# 4_Port__schdoc.net
KiCad netlist of a schematic drawn in Altium Designer
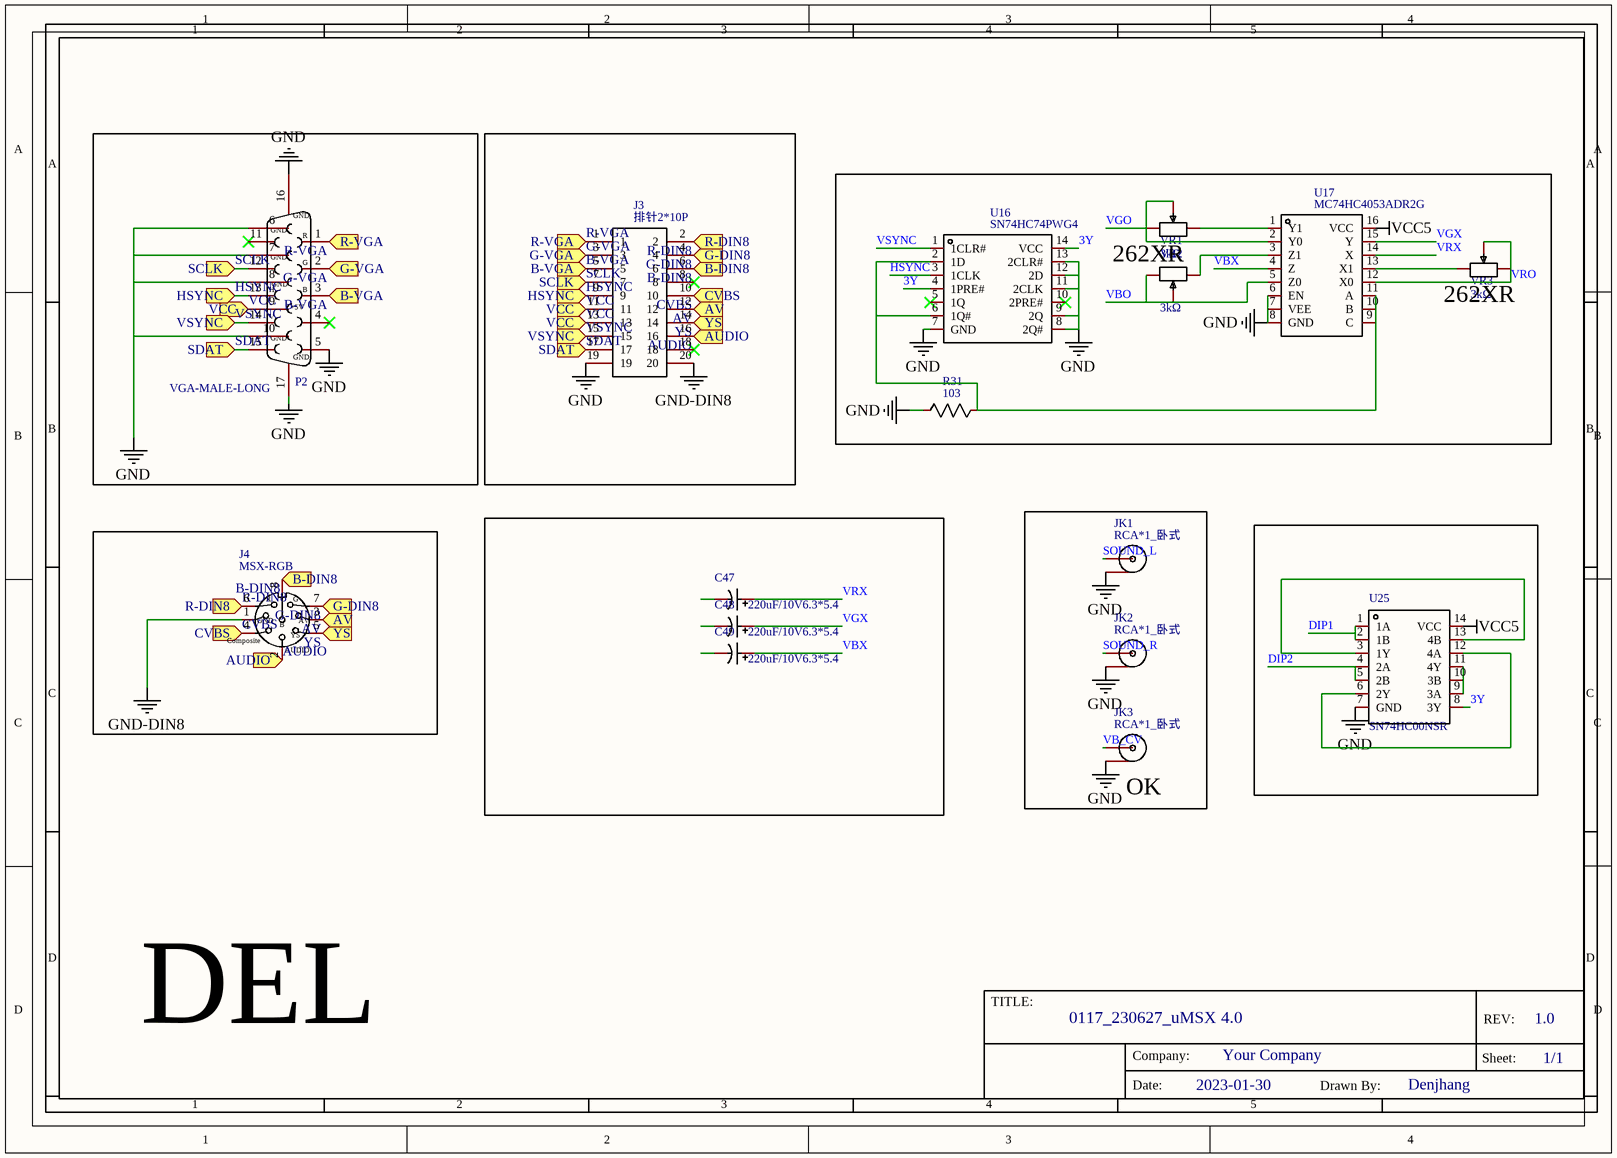
[diagram p0: 4_Port_多余的.schdoc.schdoc]

(export (version "E")
  (design (tool "Eeschema 10.0.6"))
  (components
    (comp (ref "C47")
      (value "220uF/10V6.3*5.4")
      (fields (field (name "NAME") "220uF/10V6.3*5.4"))
      (libsource (lib "altium-import") (part "root_2_固态电容220uF/10V6.3*5.4_"))
    )
    (comp (ref "C48")
      (value "220uF/10V6.3*5.4")
      (fields (field (name "NAME") "220uF/10V6.3*5.4"))
      (libsource (lib "altium-import") (part "root_2_固态电容220uF/10V6.3*5.4_"))
    )
    (comp (ref "C49")
      (value "220uF/10V6.3*5.4")
      (fields (field (name "NAME") "220uF/10V6.3*5.4"))
      (libsource (lib "altium-import") (part "root_2_固态电容220uF/10V6.3*5.4_"))
    )
    (comp (ref "J3")
      (value "排针2*10P")
      (fields (field (name "NAME") "排针2*10P"))
      (libsource (lib "altium-import") (part "root_0_排针2*10P_"))
    )
    (comp (ref "J4")
      (value "MSX-RGB")
      (fields (field (name "NAME") "MSX-RGB"))
      (libsource (lib "altium-import") (part "root_0_MSX-RGB_"))
    )
    (comp (ref "JK1")
      (value "RCA*1_卧式")
      (fields (field (name "NAME") "RCA*1_卧式"))
      (libsource (lib "altium-import") (part "root_3_RCA*1_卧式_"))
    )
    (comp (ref "JK2")
      (value "RCA*1_卧式")
      (fields (field (name "NAME") "RCA*1_卧式"))
      (libsource (lib "altium-import") (part "root_3_RCA*1_卧式_"))
    )
    (comp (ref "JK3")
      (value "RCA*1_卧式")
      (fields (field (name "NAME") "RCA*1_卧式"))
      (libsource (lib "altium-import") (part "root_3_RCA*1_卧式_"))
    )
    (comp (ref "P2")
      (value "VGA-MALE-LONG")
      (fields (field (name "NAME") "VGA-MALE-LONG"))
      (libsource (lib "altium-import") (part "root_0_VGA-MALE-LONG_"))
    )
    (comp (ref "R31")
      (value "103")
      (fields (field (name "NAME") "103"))
      (libsource (lib "altium-import") (part "root_0_103_"))
    )
    (comp (ref "U16")
      (value "SN74HC74PWG4")
      (fields (field (name "NAME") "SN74HC74PWG4") (field (name "MANUFACTURER") "TI(德州仪器)"))
      (libsource (lib "altium-import") (part "root_0_SN74HC74PWG4_"))
    )
    (comp (ref "U17")
      (value "MC74HC4053ADR2G")
      (fields (field (name "NAME") "MC74HC4053ADR2G") (field (name "MANUFACTURER") "onsemi(安森美)"))
      (libsource (lib "altium-import") (part "root_3_MC74HC4053ADR2G_"))
    )
    (comp (ref "U25")
      (value "SN74HC00NSR")
      (description "逻辑电路的归属系列:74HC;逻辑类型:与非门;")
      (fields (field (name "NAME") "SN74HC00NSR") (field (name "MANUFACTURER") "TI(德州仪器)"))
      (libsource (lib "altium-import") (part "root_0_SN74HC00NSR_"))
    )
    (comp (ref "VR1")
      (value "3kΩ")
      (fields
        (field (name "NAME") "3kΩ")
        (field (name "MANUFACTURER") "PANASONIC(松下)")
        (field (name "MANUFACTURER PART") "EVM3ESX50B33")
        (field (name "TOLERANCE") "±25%")
      )
      (libsource (lib "altium-import") (part "root_3_EVM3ESX50B33_"))
    )
    (comp (ref "VR2")
      (value "3kΩ")
      (fields
        (field (name "NAME") "3kΩ")
        (field (name "MANUFACTURER") "PANASONIC(松下)")
        (field (name "MANUFACTURER PART") "EVM3ESX50B33")
        (field (name "TOLERANCE") "±25%")
      )
      (libsource (lib "altium-import") (part "root_1_EVM3ESX50B33_"))
    )
    (comp (ref "VR3")
      (value "3kΩ")
      (fields
        (field (name "NAME") "3kΩ")
        (field (name "MANUFACTURER") "PANASONIC(松下)")
        (field (name "MANUFACTURER PART") "EVM3ESX50B33")
        (field (name "TOLERANCE") "±25%")
      )
      (libsource (lib "altium-import") (part "root_3_EVM3ESX50B33_"))
    )
  )
  (nets
    (net (code "1") (name "/3Y") (class "Default")
      (node (ref "U16") (pin "14") (pinfunction "VCC_14") (pintype "passive"))
      (node (ref "U16") (pin "4") (pinfunction "1PRE#_4") (pintype "passive"))
      (node (ref "U25") (pin "8") (pinfunction "3Y_8") (pintype "passive"))
    )
    (net (code "2") (name "/AUDIO") (class "Default")
      (node (ref "J3") (pin "16") (pinfunction "16_16") (pintype "passive"))
      (node (ref "J4") (pin "2") (pintype "passive"))
    )
    (net (code "3") (name "/AV") (class "Default")
      (node (ref "J3") (pin "12") (pinfunction "12_12") (pintype "passive"))
      (node (ref "J4") (pin "3") (pintype "passive"))
    )
    (net (code "4") (name "/B-DIN8") (class "Default")
      (node (ref "J3") (pin "6") (pinfunction "6_6") (pintype "passive"))
      (node (ref "J4") (pin "8") (pintype "passive"))
    )
    (net (code "5") (name "/B-VGA") (class "Default")
      (node (ref "J3") (pin "5") (pinfunction "5_5") (pintype "passive"))
      (node (ref "P2") (pin "3") (pinfunction "3_3") (pintype "passive"))
    )
    (net (code "6") (name "/CVBS") (class "Default")
      (node (ref "J3") (pin "10") (pinfunction "10_10") (pintype "passive"))
      (node (ref "J4") (pin "4") (pintype "passive"))
    )
    (net (code "7") (name "/DIP1") (class "Default")
      (node (ref "U25") (pin "1") (pinfunction "1A_1") (pintype "passive"))
      (node (ref "U25") (pin "2") (pinfunction "1B_2") (pintype "passive"))
    )
    (net (code "8") (name "/DIP2") (class "Default")
      (node (ref "U25") (pin "4") (pinfunction "2A_4") (pintype "passive"))
      (node (ref "U25") (pin "5") (pinfunction "2B_5") (pintype "passive"))
    )
    (net (code "9") (name "/G-DIN8") (class "Default")
      (node (ref "J3") (pin "4") (pinfunction "4_4") (pintype "passive"))
      (node (ref "J4") (pin "7") (pintype "passive"))
    )
    (net (code "10") (name "/G-VGA") (class "Default")
      (node (ref "J3") (pin "3") (pinfunction "3_3") (pintype "passive"))
      (node (ref "P2") (pin "2") (pinfunction "2_2") (pintype "passive"))
    )
    (net (code "11") (name "/HSYNC") (class "Default")
      (node (ref "J3") (pin "9") (pinfunction "9_9") (pintype "passive"))
      (node (ref "P2") (pin "13") (pinfunction "13_13") (pintype "passive"))
      (node (ref "U16") (pin "3") (pinfunction "1CLK_3") (pintype "passive"))
    )
    (net (code "12") (name "/R-DIN8") (class "Default")
      (node (ref "J3") (pin "2") (pinfunction "2_2") (pintype "passive"))
      (node (ref "J4") (pin "6") (pintype "passive"))
    )
    (net (code "13") (name "/R-VGA") (class "Default")
      (node (ref "J3") (pin "1") (pinfunction "1_1") (pintype "passive"))
      (node (ref "P2") (pin "1") (pinfunction "1_1") (pintype "passive"))
    )
    (net (code "14") (name "/SCLK") (class "Default")
      (node (ref "J3") (pin "7") (pinfunction "7_7") (pintype "passive"))
      (node (ref "P2") (pin "12") (pinfunction "12_12") (pintype "passive"))
    )
    (net (code "15") (name "/SDAT") (class "Default")
      (node (ref "J3") (pin "17") (pinfunction "17_17") (pintype "passive"))
      (node (ref "P2") (pin "15") (pinfunction "15_15") (pintype "passive"))
    )
    (net (code "16") (name "/SOUND_L") (class "Default")
      (node (ref "JK1") (pin "2") (pinfunction "2_2") (pintype "passive"))
    )
    (net (code "17") (name "/SOUND_R") (class "Default")
      (node (ref "JK2") (pin "2") (pinfunction "2_2") (pintype "passive"))
    )
    (net (code "18") (name "/VBO") (class "Default")
      (node (ref "U17") (pin "5") (pinfunction "Z0_5") (pintype "passive"))
      (node (ref "VR2") (pin "a") (pinfunction "a_a") (pintype "passive"))
      (node (ref "VR2") (pin "b") (pinfunction "b_b") (pintype "passive"))
    )
    (net (code "19") (name "/VBX") (class "Default")
      (node (ref "C49") (pin "1") (pinfunction "1_1") (pintype "passive"))
      (node (ref "U17") (pin "4") (pinfunction "Z_4") (pintype "passive"))
    )
    (net (code "20") (name "/VB_CV") (class "Default")
      (node (ref "JK3") (pin "2") (pinfunction "2_2") (pintype "passive"))
    )
    (net (code "21") (name "/VCC") (class "Default")
      (node (ref "J3") (pin "11") (pinfunction "11_11") (pintype "passive"))
      (node (ref "J3") (pin "13") (pinfunction "13_13") (pintype "passive"))
      (node (ref "P2") (pin "9") (pinfunction "9_9") (pintype "passive"))
    )
    (net (code "22") (name "/VGO") (class "Default")
      (node (ref "U17") (pin "2") (pinfunction "Y0_2") (pintype "passive"))
      (node (ref "VR1") (pin "b") (pinfunction "b_b") (pintype "passive"))
      (node (ref "VR1") (pin "c") (pinfunction "c_c") (pintype "passive"))
    )
    (net (code "23") (name "/VGX") (class "Default")
      (node (ref "C48") (pin "1") (pinfunction "1_1") (pintype "passive"))
      (node (ref "U17") (pin "15") (pinfunction "Y_15") (pintype "passive"))
    )
    (net (code "24") (name "/VRO") (class "Default")
      (node (ref "U17") (pin "12") (pinfunction "X0_12") (pintype "passive"))
      (node (ref "VR3") (pin "a") (pinfunction "a_a") (pintype "passive"))
      (node (ref "VR3") (pin "b") (pinfunction "b_b") (pintype "passive"))
    )
    (net (code "25") (name "/VRX") (class "Default")
      (node (ref "C47") (pin "1") (pinfunction "1_1") (pintype "passive"))
      (node (ref "U17") (pin "14") (pinfunction "X_14") (pintype "passive"))
    )
    (net (code "26") (name "/VSYNC") (class "Default")
      (node (ref "J3") (pin "15") (pinfunction "15_15") (pintype "passive"))
      (node (ref "P2") (pin "14") (pinfunction "14_14") (pintype "passive"))
      (node (ref "U16") (pin "1") (pinfunction "1CLR#_1") (pintype "passive"))
    )
    (net (code "27") (name "/YS") (class "Default")
      (node (ref "J3") (pin "14") (pinfunction "14_14") (pintype "passive"))
      (node (ref "J4") (pin "5") (pintype "passive"))
    )
    (net (code "28") (name "GND") (class "Default")
      (node (ref "J3") (pin "19") (pinfunction "19_19") (pintype "passive"))
      (node (ref "JK1") (pin "3") (pinfunction "3_3") (pintype "passive"))
      (node (ref "JK2") (pin "3") (pinfunction "3_3") (pintype "passive"))
      (node (ref "JK3") (pin "3") (pinfunction "3_3") (pintype "passive"))
      (node (ref "P2") (pin "10") (pinfunction "10_10") (pintype "passive"))
      (node (ref "P2") (pin "16") (pinfunction "0_16") (pintype "passive"))
      (node (ref "P2") (pin "17") (pinfunction "0_17") (pintype "passive"))
      (node (ref "P2") (pin "5") (pinfunction "5_5") (pintype "passive"))
      (node (ref "P2") (pin "6") (pinfunction "6_6") (pintype "passive"))
      (node (ref "P2") (pin "7") (pinfunction "7_7") (pintype "passive"))
      (node (ref "P2") (pin "8") (pinfunction "8_8") (pintype "passive"))
      (node (ref "R31") (pin "1") (pinfunction "1_1") (pintype "passive"))
      (node (ref "U16") (pin "11") (pinfunction "2CLK_11") (pintype "passive"))
      (node (ref "U16") (pin "12") (pinfunction "2D_12") (pintype "passive"))
      (node (ref "U16") (pin "13") (pinfunction "2CLR#_13") (pintype "passive"))
      (node (ref "U16") (pin "7") (pinfunction "GND_7") (pintype "passive"))
      (node (ref "U16") (pin "8") (pinfunction "2Q#_8") (pintype "passive"))
      (node (ref "U16") (pin "9") (pinfunction "2Q_9") (pintype "passive"))
      (node (ref "U17") (pin "6") (pinfunction "EN_6") (pintype "passive"))
      (node (ref "U17") (pin "7") (pinfunction "VEE_7") (pintype "passive"))
      (node (ref "U17") (pin "8") (pinfunction "GND_8") (pintype "passive"))
      (node (ref "U25") (pin "7") (pinfunction "GND_7") (pintype "passive"))
    )
    (net (code "29") (name "GND-DIN8") (class "Default")
      (node (ref "J3") (pin "20") (pinfunction "20_20") (pintype "passive"))
      (node (ref "J4") (pin "1") (pintype "passive"))
    )
    (net (code "30") (name "Net-(U16-1D)") (class "Default")
      (node (ref "R31") (pin "2") (pinfunction "2_2") (pintype "passive"))
      (node (ref "U16") (pin "2") (pinfunction "1D_2") (pintype "passive"))
      (node (ref "U16") (pin "6") (pinfunction "1Q#_6") (pintype "passive"))
      (node (ref "U17") (pin "10") (pinfunction "B_10") (pintype "passive"))
      (node (ref "U17") (pin "11") (pinfunction "A_11") (pintype "passive"))
      (node (ref "U17") (pin "9") (pinfunction "C_9") (pintype "passive"))
    )
    (net (code "31") (name "Net-(U17-X1)") (class "Default")
      (node (ref "U17") (pin "13") (pinfunction "X1_13") (pintype "passive"))
      (node (ref "VR3") (pin "c") (pinfunction "c_c") (pintype "passive"))
    )
    (net (code "32") (name "Net-(U17-Y1)") (class "Default")
      (node (ref "U17") (pin "1") (pinfunction "Y1_1") (pintype "passive"))
      (node (ref "VR1") (pin "a") (pinfunction "a_a") (pintype "passive"))
    )
    (net (code "33") (name "Net-(U17-Z1)") (class "Default")
      (node (ref "U17") (pin "3") (pinfunction "Z1_3") (pintype "passive"))
      (node (ref "VR2") (pin "c") (pinfunction "c_c") (pintype "passive"))
    )
    (net (code "34") (name "Net-(U25-1Y)") (class "Default")
      (node (ref "U25") (pin "13") (pinfunction "4B_13") (pintype "passive"))
      (node (ref "U25") (pin "3") (pinfunction "1Y_3") (pintype "passive"))
    )
    (net (code "35") (name "Net-(U25-2Y)") (class "Default")
      (node (ref "U25") (pin "12") (pinfunction "4A_12") (pintype "passive"))
      (node (ref "U25") (pin "6") (pinfunction "2Y_6") (pintype "passive"))
    )
    (net (code "36") (name "Net-(U25-3A)") (class "Default")
      (node (ref "U25") (pin "10") (pinfunction "3B_10") (pintype "passive"))
      (node (ref "U25") (pin "11") (pinfunction "4Y_11") (pintype "passive"))
      (node (ref "U25") (pin "9") (pinfunction "3A_9") (pintype "passive"))
    )
    (net (code "37") (name "VCC5") (class "Default")
      (node (ref "U17") (pin "16") (pinfunction "VCC_16") (pintype "passive"))
      (node (ref "U25") (pin "14") (pinfunction "VCC_14") (pintype "passive"))
    )
    (net (code "38") (name "unconnected-(C47-Pad2)") (class "Default")
      (node (ref "C47") (pin "2") (pinfunction "2_2") (pintype "passive"))
    )
    (net (code "39") (name "unconnected-(C48-Pad2)") (class "Default")
      (node (ref "C48") (pin "2") (pinfunction "2_2") (pintype "passive"))
    )
    (net (code "40") (name "unconnected-(C49-Pad2)") (class "Default")
      (node (ref "C49") (pin "2") (pinfunction "2_2") (pintype "passive"))
    )
    (net (code "41") (name "unconnected-(J3-Pad8)") (class "Default")
      (node (ref "J3") (pin "8") (pinfunction "8_8") (pintype "passive+no_connect"))
    )
    (net (code "42") (name "unconnected-(J3-Pad18)") (class "Default")
      (node (ref "J3") (pin "18") (pinfunction "18_18") (pintype "passive+no_connect"))
    )
    (net (code "43") (name "unconnected-(P2-Pad4)") (class "Default")
      (node (ref "P2") (pin "4") (pinfunction "4_4") (pintype "passive+no_connect"))
    )
    (net (code "44") (name "unconnected-(P2-Pad11)") (class "Default")
      (node (ref "P2") (pin "11") (pinfunction "11_11") (pintype "passive+no_connect"))
    )
    (net (code "45") (name "unconnected-(U16-1Q-Pad5)") (class "Default")
      (node (ref "U16") (pin "5") (pinfunction "1Q_5") (pintype "passive+no_connect"))
    )
    (net (code "46") (name "unconnected-(U16-2PRE#-Pad10)") (class "Default")
      (node (ref "U16") (pin "10") (pinfunction "2PRE#_10") (pintype "passive+no_connect"))
    )
  )
)
